# untitled.net
KiCad netlist of a schematic drawn in EAGLE
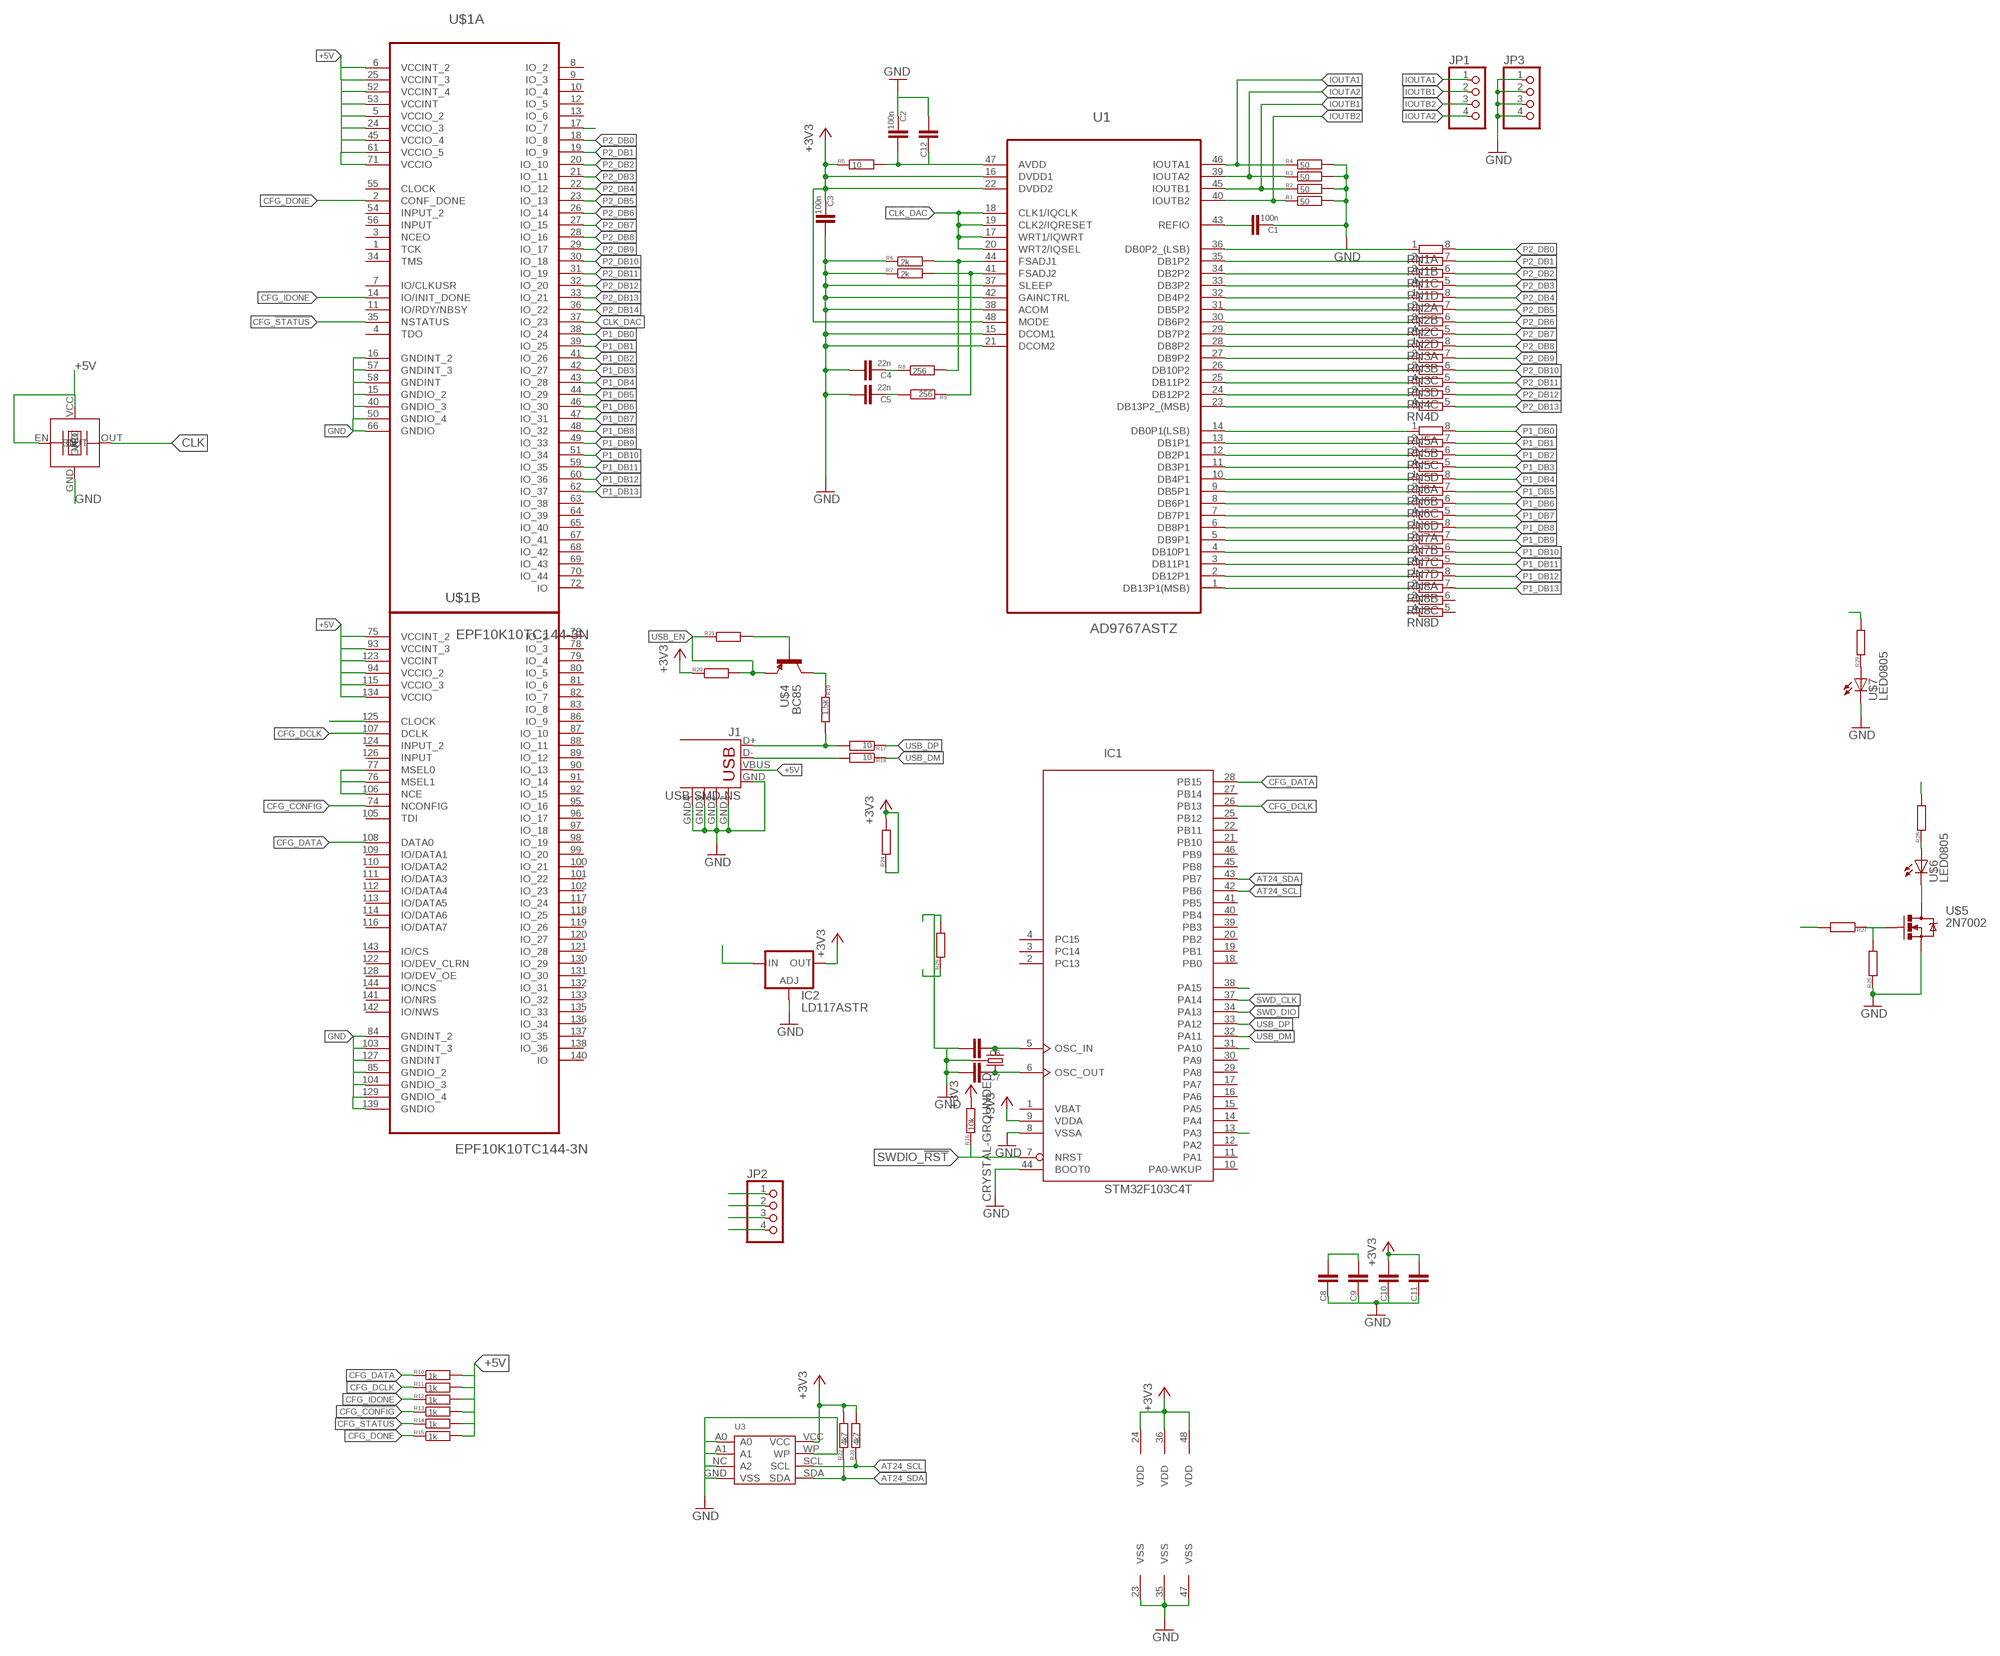
[diagram p0: schematic, sheet 1]

(export (version "E")
  (design (tool "Eeschema 10.0.6"))
  (components
    (comp (ref "C1")
      (value "100n")
      (footprint "eagle-import:C0805")
      (libsource (lib "eagle-import") (part "CC0805"))
    )
    (comp (ref "C2")
      (value "100n")
      (footprint "eagle-import:C0805")
      (libsource (lib "eagle-import") (part "CC0805"))
    )
    (comp (ref "C3")
      (value "100n")
      (footprint "eagle-import:C0805")
      (libsource (lib "eagle-import") (part "CC0805"))
    )
    (comp (ref "C4")
      (value "22n")
      (footprint "eagle-import:C0805")
      (libsource (lib "eagle-import") (part "CC0805"))
    )
    (comp (ref "C5")
      (value "22n")
      (footprint "eagle-import:C0805")
      (libsource (lib "eagle-import") (part "CC0805"))
    )
    (comp (ref "C6")
      (value "CC0603")
      (footprint "eagle-import:C0603")
      (libsource (lib "eagle-import") (part "CC0603"))
    )
    (comp (ref "C7")
      (value "CC0603")
      (footprint "eagle-import:C0603")
      (libsource (lib "eagle-import") (part "CC0603"))
    )
    (comp (ref "C8")
      (value "CC0805")
      (footprint "eagle-import:C0805")
      (libsource (lib "eagle-import") (part "CC0805"))
    )
    (comp (ref "C9")
      (value "CC0805")
      (footprint "eagle-import:C0805")
      (libsource (lib "eagle-import") (part "CC0805"))
    )
    (comp (ref "C10")
      (value "CC0805")
      (footprint "eagle-import:C0805")
      (libsource (lib "eagle-import") (part "CC0805"))
    )
    (comp (ref "C11")
      (value "CC0805")
      (footprint "eagle-import:C0805")
      (libsource (lib "eagle-import") (part "CC0805"))
    )
    (comp (ref "C12")
      (value "CC0805")
      (footprint "eagle-import:C0805")
      (libsource (lib "eagle-import") (part "CC0805"))
    )
    (comp (ref "IC1")
      (value "STM32F103C4T")
      (footprint "eagle-import:LQFP48")
      (libsource (lib "eagle-import") (part "STM32F103CT4"))
    )
    (comp (ref "IC2")
      (value "LD117ASTR")
      (footprint "eagle-import:SOT223")
      (libsource (lib "eagle-import") (part "LD117A?STR"))
    )
    (comp (ref "J1")
      (value "USB-SMD-NS")
      (footprint "eagle-import:USB-MINIB-NOSTOP")
      (libsource (lib "eagle-import") (part "USB-SMD-NS"))
    )
    (comp (ref "JP1")
      (value "PINHD-1X04_2.54")
      (footprint "eagle-import:1X04")
      (libsource (lib "eagle-import") (part "PINHD-1X04_2.54"))
    )
    (comp (ref "JP2")
      (value "PINHD-1X04_2.54")
      (footprint "eagle-import:1X04")
      (libsource (lib "eagle-import") (part "PINHD-1X04_2.54"))
    )
    (comp (ref "JP3")
      (value "PINHD-1X04_2.54")
      (footprint "eagle-import:1X04")
      (libsource (lib "eagle-import") (part "PINHD-1X04_2.54"))
    )
    (comp (ref "R1")
      (value "50")
      (footprint "eagle-import:R0805")
      (libsource (lib "eagle-import") (part "R0805"))
    )
    (comp (ref "R2")
      (value "50")
      (footprint "eagle-import:R0805")
      (libsource (lib "eagle-import") (part "R0805"))
    )
    (comp (ref "R3")
      (value "50")
      (footprint "eagle-import:R0805")
      (libsource (lib "eagle-import") (part "R0805"))
    )
    (comp (ref "R4")
      (value "50")
      (footprint "eagle-import:R0805")
      (libsource (lib "eagle-import") (part "R0805"))
    )
    (comp (ref "R5")
      (value "10")
      (footprint "eagle-import:R0805")
      (libsource (lib "eagle-import") (part "R0805"))
    )
    (comp (ref "R6")
      (value "2k")
      (footprint "eagle-import:R0805")
      (libsource (lib "eagle-import") (part "R0805"))
    )
    (comp (ref "R7")
      (value "2k")
      (footprint "eagle-import:R0805")
      (libsource (lib "eagle-import") (part "R0805"))
    )
    (comp (ref "R8")
      (value "256")
      (footprint "eagle-import:R0805")
      (libsource (lib "eagle-import") (part "R0805"))
    )
    (comp (ref "R9")
      (value "256")
      (footprint "eagle-import:R0805")
      (libsource (lib "eagle-import") (part "R0805"))
    )
    (comp (ref "R10")
      (value "1k")
      (footprint "eagle-import:0603")
      (libsource (lib "eagle-import") (part "R0603"))
    )
    (comp (ref "R11")
      (value "1k")
      (footprint "eagle-import:0603")
      (libsource (lib "eagle-import") (part "R0603"))
    )
    (comp (ref "R12")
      (value "1k")
      (footprint "eagle-import:0603")
      (libsource (lib "eagle-import") (part "R0603"))
    )
    (comp (ref "R13")
      (value "1k")
      (footprint "eagle-import:0603")
      (libsource (lib "eagle-import") (part "R0603"))
    )
    (comp (ref "R14")
      (value "1k")
      (footprint "eagle-import:0603")
      (libsource (lib "eagle-import") (part "R0603"))
    )
    (comp (ref "R15")
      (value "1k")
      (footprint "eagle-import:0603")
      (libsource (lib "eagle-import") (part "R0603"))
    )
    (comp (ref "R16")
      (value "10k")
      (footprint "eagle-import:0603")
      (libsource (lib "eagle-import") (part "R0603"))
    )
    (comp (ref "R17")
      (value "10")
      (footprint "eagle-import:0603")
      (libsource (lib "eagle-import") (part "R0603"))
    )
    (comp (ref "R18")
      (value "10")
      (footprint "eagle-import:0603")
      (libsource (lib "eagle-import") (part "R0603"))
    )
    (comp (ref "R19")
      (value "1.5k")
      (footprint "eagle-import:0603")
      (libsource (lib "eagle-import") (part "R0603"))
    )
    (comp (ref "R20")
      (value "R0603")
      (footprint "eagle-import:0603")
      (libsource (lib "eagle-import") (part "R0603"))
    )
    (comp (ref "R21")
      (value "R0603")
      (footprint "eagle-import:0603")
      (libsource (lib "eagle-import") (part "R0603"))
    )
    (comp (ref "R22")
      (value "4k7")
      (footprint "eagle-import:0603")
      (libsource (lib "eagle-import") (part "R0603"))
    )
    (comp (ref "R23")
      (value "4k7")
      (footprint "eagle-import:0603")
      (libsource (lib "eagle-import") (part "R0603"))
    )
    (comp (ref "R24")
      (value "R1206")
      (footprint "eagle-import:R1206")
      (libsource (lib "eagle-import") (part "R1206"))
    )
    (comp (ref "R25")
      (value "R0603")
      (footprint "eagle-import:0603")
      (libsource (lib "eagle-import") (part "R0603"))
    )
    (comp (ref "R26")
      (value "R0603")
      (footprint "eagle-import:0603")
      (libsource (lib "eagle-import") (part "R0603"))
    )
    (comp (ref "R27")
      (value "R0603")
      (footprint "eagle-import:0603")
      (libsource (lib "eagle-import") (part "R0603"))
    )
    (comp (ref "R28")
      (value "R0603")
      (footprint "eagle-import:0603")
      (libsource (lib "eagle-import") (part "R0603"))
    )
    (comp (ref "R29")
      (value "R0603")
      (footprint "eagle-import:0603")
      (libsource (lib "eagle-import") (part "R0603"))
    )
    (comp (ref "RN1")
      (value "4R-N0402ARV341")
      (footprint "eagle-import:4X0402ARV341")
      (libsource (lib "eagle-import") (part "4R-N0402ARV341"))
    )
    (comp (ref "RN2")
      (value "4R-N0402ARV341")
      (footprint "eagle-import:4X0402ARV341")
      (libsource (lib "eagle-import") (part "4R-N0402ARV341"))
    )
    (comp (ref "RN3")
      (value "4R-N0402ARV341")
      (footprint "eagle-import:4X0402ARV341")
      (libsource (lib "eagle-import") (part "4R-N0402ARV341"))
    )
    (comp (ref "RN4")
      (value "4R-N0402ARV341")
      (footprint "eagle-import:4X0402ARV341")
      (libsource (lib "eagle-import") (part "4R-N0402ARV341"))
    )
    (comp (ref "RN5")
      (value "4R-N0402ARV341")
      (footprint "eagle-import:4X0402ARV341")
      (libsource (lib "eagle-import") (part "4R-N0402ARV341"))
    )
    (comp (ref "RN6")
      (value "4R-N0402ARV341")
      (footprint "eagle-import:4X0402ARV341")
      (libsource (lib "eagle-import") (part "4R-N0402ARV341"))
    )
    (comp (ref "RN7")
      (value "4R-N0402ARV341")
      (footprint "eagle-import:4X0402ARV341")
      (libsource (lib "eagle-import") (part "4R-N0402ARV341"))
    )
    (comp (ref "RN8")
      (value "4R-N0402ARV341")
      (footprint "eagle-import:4X0402ARV341")
      (libsource (lib "eagle-import") (part "4R-N0402ARV341"))
    )
    (comp (ref "U$1")
      (value "EPF10K10TC144-3N")
      (footprint "eagle-import:QFP50P2200X2200X160-144N")
      (libsource (lib "eagle-import") (part "EPF10K10TC144-3N"))
    )
    (comp (ref "U$2")
      (value "TXC-BA")
      (footprint "eagle-import:7X5")
      (libsource (lib "eagle-import") (part "TXC-BA"))
    )
    (comp (ref "U$3")
      (value "CRYSTAL-GROUNDED")
      (footprint "eagle-import:CRYSTAL-SMD-5X3")
      (libsource (lib "eagle-import") (part "CRYSTAL-GROUNDED"))
    )
    (comp (ref "U$4")
      (value "BC85")
      (footprint "eagle-import:SOT23")
      (libsource (lib "eagle-import") (part "BC85"))
    )
    (comp (ref "U$5")
      (value "2N7002")
      (footprint "eagle-import:SOT23")
      (libsource (lib "eagle-import") (part "2N7002"))
    )
    (comp (ref "U$6")
      (value "LED0805")
      (footprint "eagle-import:0805-LED")
      (libsource (lib "eagle-import") (part "LED0805"))
    )
    (comp (ref "U$7")
      (value "LED0805")
      (footprint "eagle-import:0805-LED")
      (libsource (lib "eagle-import") (part "LED0805"))
    )
    (comp (ref "U1")
      (value "AD9767ASTZ")
      (footprint "eagle-import:QFP50P900X900X160-48N")
      (libsource (lib "eagle-import") (part "AD9767ASTZ"))
    )
    (comp (ref "U3")
      (value "EEPROM-CAT24C256WI-GT3(SOIC8)QFN")
      (footprint "eagle-import:QFN")
      (libsource (lib "eagle-import") (part "EEPROM-CAT24C256WI-GT3(SOIC8)QFN"))
    )
  )
  (nets
    (net (code "1") (name "+3V3") (class "Default")
      (node (ref "C10") (pin "1") (pinfunction "1_1") (pintype "passive"))
      (node (ref "C11") (pin "1") (pinfunction "1_1") (pintype "passive"))
      (node (ref "C3") (pin "2") (pinfunction "2_2") (pintype "passive"))
      (node (ref "IC1") (pin "24") (pinfunction "VDD_24") (pintype "power_in"))
      (node (ref "IC1") (pin "36") (pinfunction "VDD_36") (pintype "power_in"))
      (node (ref "IC1") (pin "48") (pinfunction "VDD_48") (pintype "power_in"))
      (node (ref "IC1") (pin "9") (pinfunction "VDDA_9") (pintype "power_in"))
      (node (ref "IC2") (pin "4") (pinfunction "OUT_4") (pintype "passive"))
      (node (ref "R16") (pin "2") (pinfunction "2_2") (pintype "passive"))
      (node (ref "R20") (pin "1") (pinfunction "1_1") (pintype "passive"))
      (node (ref "R22") (pin "2") (pinfunction "2_2") (pintype "passive"))
      (node (ref "R23") (pin "2") (pinfunction "2_2") (pintype "passive"))
      (node (ref "R24") (pin "1") (pinfunction "1_1") (pintype "passive"))
      (node (ref "R24") (pin "2") (pinfunction "2_2") (pintype "passive"))
      (node (ref "R5") (pin "1") (pinfunction "1_1") (pintype "passive"))
      (node (ref "U1") (pin "16") (pinfunction "DVDD1_16") (pintype "power_in"))
      (node (ref "U1") (pin "22") (pinfunction "DVDD2_22") (pintype "power_in"))
      (node (ref "U1") (pin "48") (pinfunction "MODE_48") (pintype "passive"))
      (node (ref "U3") (pin "VCC") (pinfunction "VCC_VCC") (pintype "bidirectional"))
    )
    (net (code "2") (name "+5V") (class "Default")
      (node (ref "C8") (pin "1") (pinfunction "1_1") (pintype "passive"))
      (node (ref "C9") (pin "1") (pinfunction "1_1") (pintype "passive"))
      (node (ref "IC2") (pin "3") (pinfunction "IN_3") (pintype "input"))
      (node (ref "J1") (pin "VBUS") (pinfunction "VBUS_VBUS") (pintype "bidirectional"))
      (node (ref "R10") (pin "2") (pinfunction "2_2") (pintype "passive"))
      (node (ref "R11") (pin "2") (pinfunction "2_2") (pintype "passive"))
      (node (ref "R12") (pin "2") (pinfunction "2_2") (pintype "passive"))
      (node (ref "R13") (pin "2") (pinfunction "2_2") (pintype "passive"))
      (node (ref "R14") (pin "2") (pinfunction "2_2") (pintype "passive"))
      (node (ref "R15") (pin "2") (pinfunction "2_2") (pintype "passive"))
      (node (ref "R28") (pin "2") (pinfunction "2_2") (pintype "passive"))
      (node (ref "U$1") (pin "115") (pinfunction "VCCIO_3_115") (pintype "power_in"))
      (node (ref "U$1") (pin "123") (pinfunction "VCCINT_123") (pintype "power_in"))
      (node (ref "U$1") (pin "134") (pinfunction "VCCIO_134") (pintype "power_in"))
      (node (ref "U$1") (pin "24") (pinfunction "VCCIO_3_24") (pintype "power_in"))
      (node (ref "U$1") (pin "25") (pinfunction "VCCINT_3_25") (pintype "power_in"))
      (node (ref "U$1") (pin "45") (pinfunction "VCCIO_4_45") (pintype "power_in"))
      (node (ref "U$1") (pin "5") (pinfunction "VCCIO_2_5") (pintype "power_in"))
      (node (ref "U$1") (pin "52") (pinfunction "VCCINT_4_52") (pintype "power_in"))
      (node (ref "U$1") (pin "53") (pinfunction "VCCINT_53") (pintype "power_in"))
      (node (ref "U$1") (pin "6") (pinfunction "VCCINT_2_6") (pintype "power_in"))
      (node (ref "U$1") (pin "61") (pinfunction "VCCIO_5_61") (pintype "power_in"))
      (node (ref "U$1") (pin "71") (pinfunction "VCCIO_71") (pintype "power_in"))
      (node (ref "U$1") (pin "75") (pinfunction "VCCINT_2_75") (pintype "power_in"))
      (node (ref "U$1") (pin "93") (pinfunction "VCCINT_3_93") (pintype "power_in"))
      (node (ref "U$1") (pin "94") (pinfunction "VCCIO_2_94") (pintype "power_in"))
      (node (ref "U$2") (pin "EN") (pinfunction "EN_EN") (pintype "bidirectional"))
      (node (ref "U$2") (pin "VCC") (pinfunction "VCC_VCC") (pintype "bidirectional"))
    )
    (net (code "3") (name "/CFG_~{CONFIG}") (class "Default")
      (node (ref "IC1") (pin "31") (pinfunction "PA10_31") (pintype "bidirectional"))
      (node (ref "R13") (pin "1") (pinfunction "1_1") (pintype "passive"))
      (node (ref "U$1") (pin "74") (pinfunction "NCONFIG_74") (pintype "input"))
    )
    (net (code "4") (name "/CFG_~{STATUS}") (class "Default")
      (node (ref "R14") (pin "1") (pinfunction "1_1") (pintype "passive"))
      (node (ref "U$1") (pin "35") (pinfunction "NSTATUS_35") (pintype "output"))
    )
    (net (code "5") (name "/IO7") (class "Default")
      (node (ref "R29") (pin "2") (pinfunction "2_2") (pintype "passive"))
      (node (ref "U$1") (pin "17") (pinfunction "IO_7_17") (pintype "bidirectional"))
    )
    (net (code "6") (name "/SWDIO_~{RST}") (class "Default")
      (node (ref "IC1") (pin "7") (pinfunction "NRST_7") (pintype "bidirectional"))
      (node (ref "JP2") (pin "4") (pinfunction "4_4") (pintype "passive"))
      (node (ref "R16") (pin "1") (pinfunction "1_1") (pintype "passive"))
    )
    (net (code "7") (name "/VBAT") (class "Default")
      (node (ref "IC1") (pin "1") (pinfunction "VBAT_1") (pintype "power_in"))
    )
    (net (code "8") (name "AT24_SCL") (class "Default")
      (node (ref "IC1") (pin "42") (pinfunction "PB6_42") (pintype "bidirectional"))
      (node (ref "R23") (pin "1") (pinfunction "1_1") (pintype "passive"))
      (node (ref "U3") (pin "SCL") (pinfunction "SCL_SCL") (pintype "bidirectional"))
    )
    (net (code "9") (name "AT24_SDA") (class "Default")
      (node (ref "IC1") (pin "43") (pinfunction "PB7_43") (pintype "bidirectional"))
      (node (ref "R22") (pin "1") (pinfunction "1_1") (pintype "passive"))
      (node (ref "U3") (pin "SDA") (pinfunction "SDA_SDA") (pintype "bidirectional"))
    )
    (net (code "10") (name "CFG_DATA") (class "Default")
      (node (ref "IC1") (pin "28") (pinfunction "PB15_28") (pintype "bidirectional"))
      (node (ref "R10") (pin "1") (pinfunction "1_1") (pintype "passive"))
      (node (ref "U$1") (pin "108") (pinfunction "DATA0_108") (pintype "bidirectional"))
    )
    (net (code "11") (name "CFG_DCLK") (class "Default")
      (node (ref "IC1") (pin "26") (pinfunction "PB13_26") (pintype "bidirectional"))
      (node (ref "R11") (pin "1") (pinfunction "1_1") (pintype "passive"))
      (node (ref "U$1") (pin "107") (pinfunction "DCLK_107") (pintype "input"))
    )
    (net (code "12") (name "CFG_DONE") (class "Default")
      (node (ref "R15") (pin "1") (pinfunction "1_1") (pintype "passive"))
      (node (ref "R27") (pin "2") (pinfunction "2_2") (pintype "passive"))
      (node (ref "U$1") (pin "2") (pinfunction "CONF_DONE_2") (pintype "input"))
    )
    (net (code "13") (name "CFG_IDONE") (class "Default")
      (node (ref "R12") (pin "1") (pinfunction "1_1") (pintype "passive"))
      (node (ref "U$1") (pin "14") (pinfunction "IO/INIT_DONE_14") (pintype "bidirectional"))
    )
    (net (code "14") (name "CLK") (class "Default")
      (node (ref "U$1") (pin "125") (pinfunction "CLOCK_125") (pintype "input"))
      (node (ref "U$2") (pin "OUT") (pinfunction "OUT_OUT") (pintype "bidirectional"))
    )
    (net (code "15") (name "CLK_DAC") (class "Default")
      (node (ref "U$1") (pin "37") (pinfunction "IO_23_37") (pintype "bidirectional"))
      (node (ref "U1") (pin "17") (pinfunction "WRT1/IQWRT_17") (pintype "input"))
      (node (ref "U1") (pin "18") (pinfunction "CLK1/IQCLK_18") (pintype "input"))
      (node (ref "U1") (pin "19") (pinfunction "CLK2/IQRESET_19") (pintype "input"))
      (node (ref "U1") (pin "20") (pinfunction "WRT2/IQSEL_20") (pintype "input"))
    )
    (net (code "16") (name "GND") (class "Default")
      (node (ref "C1") (pin "2") (pinfunction "2_2") (pintype "passive"))
      (node (ref "C10") (pin "2") (pinfunction "2_2") (pintype "passive"))
      (node (ref "C11") (pin "2") (pinfunction "2_2") (pintype "passive"))
      (node (ref "C12") (pin "1") (pinfunction "1_1") (pintype "passive"))
      (node (ref "C2") (pin "2") (pinfunction "2_2") (pintype "passive"))
      (node (ref "C3") (pin "1") (pinfunction "1_1") (pintype "passive"))
      (node (ref "C4") (pin "1") (pinfunction "1_1") (pintype "passive"))
      (node (ref "C5") (pin "1") (pinfunction "1_1") (pintype "passive"))
      (node (ref "C6") (pin "1") (pinfunction "1_1") (pintype "passive"))
      (node (ref "C7") (pin "1") (pinfunction "1_1") (pintype "passive"))
      (node (ref "C8") (pin "2") (pinfunction "2_2") (pintype "passive"))
      (node (ref "C9") (pin "2") (pinfunction "2_2") (pintype "passive"))
      (node (ref "IC1") (pin "23") (pinfunction "VSS_23") (pintype "power_in"))
      (node (ref "IC1") (pin "35") (pinfunction "VSS_35") (pintype "power_in"))
      (node (ref "IC1") (pin "38") (pinfunction "PA15_38") (pintype "bidirectional"))
      (node (ref "IC1") (pin "44") (pinfunction "BOOT0_44") (pintype "input"))
      (node (ref "IC1") (pin "47") (pinfunction "VSS_47") (pintype "power_in"))
      (node (ref "IC1") (pin "8") (pinfunction "VSSA_8") (pintype "power_in"))
      (node (ref "IC2") (pin "1") (pinfunction "ADJ_1") (pintype "input"))
      (node (ref "J1") (pin "GND") (pinfunction "GND_GND") (pintype "bidirectional"))
      (node (ref "J1") (pin "GND1") (pinfunction "GND_GND1") (pintype "bidirectional"))
      (node (ref "J1") (pin "GND2") (pinfunction "GND_GND2") (pintype "bidirectional"))
      (node (ref "J1") (pin "GND3") (pinfunction "GND_GND3") (pintype "bidirectional"))
      (node (ref "J1") (pin "GND4") (pinfunction "GND_GND4") (pintype "bidirectional"))
      (node (ref "JP2") (pin "1") (pinfunction "1_1") (pintype "passive"))
      (node (ref "JP3") (pin "1") (pinfunction "1_1") (pintype "passive"))
      (node (ref "JP3") (pin "2") (pinfunction "2_2") (pintype "passive"))
      (node (ref "JP3") (pin "3") (pinfunction "3_3") (pintype "passive"))
      (node (ref "JP3") (pin "4") (pinfunction "4_4") (pintype "passive"))
      (node (ref "R1") (pin "2") (pinfunction "2_2") (pintype "passive"))
      (node (ref "R2") (pin "2") (pinfunction "2_2") (pintype "passive"))
      (node (ref "R25") (pin "1") (pinfunction "1_1") (pintype "passive"))
      (node (ref "R26") (pin "1") (pinfunction "1_1") (pintype "passive"))
      (node (ref "R26") (pin "2") (pinfunction "2_2") (pintype "passive"))
      (node (ref "R3") (pin "2") (pinfunction "2_2") (pintype "passive"))
      (node (ref "R4") (pin "2") (pinfunction "2_2") (pintype "passive"))
      (node (ref "R6") (pin "1") (pinfunction "1_1") (pintype "passive"))
      (node (ref "R7") (pin "1") (pinfunction "1_1") (pintype "passive"))
      (node (ref "U$1") (pin "103") (pinfunction "GNDINT_3_103") (pintype "passive"))
      (node (ref "U$1") (pin "104") (pinfunction "GNDIO_3_104") (pintype "passive"))
      (node (ref "U$1") (pin "106") (pinfunction "NCE_106") (pintype "input"))
      (node (ref "U$1") (pin "127") (pinfunction "GNDINT_127") (pintype "passive"))
      (node (ref "U$1") (pin "129") (pinfunction "GNDIO_4_129") (pintype "passive"))
      (node (ref "U$1") (pin "139") (pinfunction "GNDIO_139") (pintype "passive"))
      (node (ref "U$1") (pin "15") (pinfunction "GNDIO_2_15") (pintype "passive"))
      (node (ref "U$1") (pin "16") (pinfunction "GNDINT_2_16") (pintype "passive"))
      (node (ref "U$1") (pin "40") (pinfunction "GNDIO_3_40") (pintype "passive"))
      (node (ref "U$1") (pin "50") (pinfunction "GNDIO_4_50") (pintype "passive"))
      (node (ref "U$1") (pin "57") (pinfunction "GNDINT_3_57") (pintype "passive"))
      (node (ref "U$1") (pin "58") (pinfunction "GNDINT_58") (pintype "passive"))
      (node (ref "U$1") (pin "66") (pinfunction "GNDIO_66") (pintype "passive"))
      (node (ref "U$1") (pin "76") (pinfunction "MSEL1_76") (pintype "input"))
      (node (ref "U$1") (pin "77") (pinfunction "MSEL0_77") (pintype "input"))
      (node (ref "U$1") (pin "84") (pinfunction "GNDINT_2_84") (pintype "passive"))
      (node (ref "U$1") (pin "85") (pinfunction "GNDIO_2_85") (pintype "passive"))
      (node (ref "U$2") (pin "GND") (pinfunction "GND_GND") (pintype "bidirectional"))
      (node (ref "U$3") (pin "2") (pinfunction "3_2") (pintype "passive"))
      (node (ref "U$3") (pin "4") (pinfunction "3_4") (pintype "passive"))
      (node (ref "U$5") (pin "2") (pinfunction "S_2") (pintype "passive"))
      (node (ref "U$7") (pin "C") (pinfunction "C_C") (pintype "passive"))
      (node (ref "U1") (pin "15") (pinfunction "DCOM1_15") (pintype "passive"))
      (node (ref "U1") (pin "21") (pinfunction "DCOM2_21") (pintype "passive"))
      (node (ref "U1") (pin "37") (pinfunction "SLEEP_37") (pintype "passive"))
      (node (ref "U1") (pin "38") (pinfunction "ACOM_38") (pintype "passive"))
      (node (ref "U1") (pin "42") (pinfunction "GAINCTRL_42") (pintype "passive"))
      (node (ref "U3") (pin "A0") (pinfunction "A0_A0") (pintype "bidirectional"))
      (node (ref "U3") (pin "A1") (pinfunction "A1_A1") (pintype "bidirectional"))
      (node (ref "U3") (pin "GND") (pinfunction "VSS_GND") (pintype "bidirectional"))
      (node (ref "U3") (pin "NC") (pinfunction "A2_NC") (pintype "bidirectional"))
      (node (ref "U3") (pin "WP") (pinfunction "WP_WP") (pintype "bidirectional"))
    )
    (net (code "17") (name "IOUTA1") (class "Default")
      (node (ref "JP1") (pin "1") (pinfunction "1_1") (pintype "passive"))
      (node (ref "R4") (pin "1") (pinfunction "1_1") (pintype "passive"))
      (node (ref "U1") (pin "46") (pinfunction "IOUTA1_46") (pintype "output"))
    )
    (net (code "18") (name "IOUTA2") (class "Default")
      (node (ref "JP1") (pin "4") (pinfunction "4_4") (pintype "passive"))
      (node (ref "R3") (pin "1") (pinfunction "1_1") (pintype "passive"))
      (node (ref "U1") (pin "39") (pinfunction "IOUTA2_39") (pintype "output"))
    )
    (net (code "19") (name "IOUTB1") (class "Default")
      (node (ref "JP1") (pin "2") (pinfunction "2_2") (pintype "passive"))
      (node (ref "R2") (pin "1") (pinfunction "1_1") (pintype "passive"))
      (node (ref "U1") (pin "45") (pinfunction "IOUTB1_45") (pintype "output"))
    )
    (net (code "20") (name "IOUTB2") (class "Default")
      (node (ref "JP1") (pin "3") (pinfunction "3_3") (pintype "passive"))
      (node (ref "R1") (pin "1") (pinfunction "1_1") (pintype "passive"))
      (node (ref "U1") (pin "40") (pinfunction "IOUTB2_40") (pintype "output"))
    )
    (net (code "21") (name "Net-(C4-Pad2)") (class "Default")
      (node (ref "C4") (pin "2") (pinfunction "2_2") (pintype "passive"))
      (node (ref "R8") (pin "1") (pinfunction "1_1") (pintype "passive"))
    )
    (net (code "22") (name "Net-(C5-Pad2)") (class "Default")
      (node (ref "C5") (pin "2") (pinfunction "2_2") (pintype "passive"))
      (node (ref "R9") (pin "2") (pinfunction "2_2") (pintype "passive"))
    )
    (net (code "23") (name "Net-(IC1A-OSC_IN)") (class "Default")
      (node (ref "C6") (pin "2") (pinfunction "2_2") (pintype "passive"))
      (node (ref "IC1") (pin "5") (pinfunction "OSC_IN_5") (pintype "bidirectional"))
      (node (ref "U$3") (pin "3") (pinfunction "1_3") (pintype "passive"))
    )
    (net (code "24") (name "Net-(IC1A-OSC_OUT)") (class "Default")
      (node (ref "C7") (pin "2") (pinfunction "2_2") (pintype "passive"))
      (node (ref "IC1") (pin "6") (pinfunction "OSC_OUT_6") (pintype "bidirectional"))
      (node (ref "U$3") (pin "1") (pinfunction "2_1") (pintype "passive"))
    )
    (net (code "25") (name "Net-(J1-PadD+)") (class "Default")
      (node (ref "J1") (pin "D+") (pinfunction "D+_D+") (pintype "bidirectional"))
      (node (ref "R17") (pin "2") (pinfunction "2_2") (pintype "passive"))
      (node (ref "R19") (pin "2") (pinfunction "2_2") (pintype "passive"))
    )
    (net (code "26") (name "Net-(J1-PadD-)") (class "Default")
      (node (ref "J1") (pin "D-") (pinfunction "D-_D-") (pintype "bidirectional"))
      (node (ref "R18") (pin "2") (pinfunction "2_2") (pintype "passive"))
    )
    (net (code "27") (name "Net-(R28-Pad1)") (class "Default")
      (node (ref "R28") (pin "1") (pinfunction "1_1") (pintype "passive"))
      (node (ref "U$6") (pin "A") (pinfunction "A_A") (pintype "passive"))
    )
    (net (code "28") (name "Net-(R29-Pad1)") (class "Default")
      (node (ref "R29") (pin "1") (pinfunction "1_1") (pintype "passive"))
      (node (ref "U$7") (pin "A") (pinfunction "A_A") (pintype "passive"))
    )
    (net (code "29") (name "Net-(RN1B-1)") (class "Default")
      (node (ref "RN1") (pin "2") (pinfunction "1_2") (pintype "passive"))
      (node (ref "U1") (pin "35") (pinfunction "DB1P2_35") (pintype "bidirectional"))
    )
    (net (code "30") (name "Net-(RN1C-1)") (class "Default")
      (node (ref "RN1") (pin "3") (pinfunction "1_3") (pintype "passive"))
      (node (ref "U1") (pin "34") (pinfunction "DB2P2_34") (pintype "bidirectional"))
    )
    (net (code "31") (name "Net-(RN1D-1)") (class "Default")
      (node (ref "RN1") (pin "4") (pinfunction "1_4") (pintype "passive"))
      (node (ref "U1") (pin "33") (pinfunction "DB3P2_33") (pintype "bidirectional"))
    )
    (net (code "32") (name "Net-(RN2B-1)") (class "Default")
      (node (ref "RN2") (pin "2") (pinfunction "1_2") (pintype "passive"))
      (node (ref "U1") (pin "31") (pinfunction "DB5P2_31") (pintype "bidirectional"))
    )
    (net (code "33") (name "Net-(RN2C-1)") (class "Default")
      (node (ref "RN2") (pin "3") (pinfunction "1_3") (pintype "passive"))
      (node (ref "U1") (pin "30") (pinfunction "DB6P2_30") (pintype "bidirectional"))
    )
    (net (code "34") (name "Net-(RN2D-1)") (class "Default")
      (node (ref "RN2") (pin "4") (pinfunction "1_4") (pintype "passive"))
      (node (ref "U1") (pin "29") (pinfunction "DB7P2_29") (pintype "bidirectional"))
    )
    (net (code "35") (name "Net-(RN3B-1)") (class "Default")
      (node (ref "RN3") (pin "2") (pinfunction "1_2") (pintype "passive"))
      (node (ref "U1") (pin "27") (pinfunction "DB9P2_27") (pintype "bidirectional"))
    )
    (net (code "36") (name "Net-(RN3C-1)") (class "Default")
      (node (ref "RN3") (pin "3") (pinfunction "1_3") (pintype "passive"))
      (node (ref "U1") (pin "26") (pinfunction "DB10P2_26") (pintype "bidirectional"))
    )
    (net (code "37") (name "Net-(RN3D-1)") (class "Default")
      (node (ref "RN3") (pin "4") (pinfunction "1_4") (pintype "passive"))
      (node (ref "U1") (pin "25") (pinfunction "DB11P2_25") (pintype "bidirectional"))
    )
    (net (code "38") (name "Net-(RN4C-1)") (class "Default")
      (node (ref "RN4") (pin "3") (pinfunction "1_3") (pintype "passive"))
      (node (ref "U1") (pin "24") (pinfunction "DB12P2_24") (pintype "bidirectional"))
    )
    (net (code "39") (name "Net-(RN4D-1)") (class "Default")
      (node (ref "RN4") (pin "4") (pinfunction "1_4") (pintype "passive"))
      (node (ref "U1") (pin "23") (pinfunction "DB13P2_(MSB)_23") (pintype "bidirectional"))
    )
    (net (code "40") (name "Net-(RN5B-1)") (class "Default")
      (node (ref "RN5") (pin "2") (pinfunction "1_2") (pintype "passive"))
      (node (ref "U1") (pin "13") (pinfunction "DB1P1_13") (pintype "bidirectional"))
    )
    (net (code "41") (name "Net-(RN5C-1)") (class "Default")
      (node (ref "RN5") (pin "3") (pinfunction "1_3") (pintype "passive"))
      (node (ref "U1") (pin "12") (pinfunction "DB2P1_12") (pintype "bidirectional"))
    )
    (net (code "42") (name "Net-(RN5D-1)") (class "Default")
      (node (ref "RN5") (pin "4") (pinfunction "1_4") (pintype "passive"))
      (node (ref "U1") (pin "11") (pinfunction "DB3P1_11") (pintype "bidirectional"))
    )
    (net (code "43") (name "Net-(RN6B-1)") (class "Default")
      (node (ref "RN6") (pin "2") (pinfunction "1_2") (pintype "passive"))
      (node (ref "U1") (pin "9") (pinfunction "DB5P1_9") (pintype "bidirectional"))
    )
    (net (code "44") (name "Net-(RN6C-1)") (class "Default")
      (node (ref "RN6") (pin "3") (pinfunction "1_3") (pintype "passive"))
      (node (ref "U1") (pin "8") (pinfunction "DB6P1_8") (pintype "bidirectional"))
    )
    (net (code "45") (name "Net-(RN6D-1)") (class "Default")
      (node (ref "RN6") (pin "4") (pinfunction "1_4") (pintype "passive"))
      (node (ref "U1") (pin "7") (pinfunction "DB7P1_7") (pintype "bidirectional"))
    )
    (net (code "46") (name "Net-(RN7B-1)") (class "Default")
      (node (ref "RN7") (pin "2") (pinfunction "1_2") (pintype "passive"))
      (node (ref "U1") (pin "5") (pinfunction "DB9P1_5") (pintype "bidirectional"))
    )
    (net (code "47") (name "Net-(RN7C-1)") (class "Default")
      (node (ref "RN7") (pin "3") (pinfunction "1_3") (pintype "passive"))
      (node (ref "U1") (pin "4") (pinfunction "DB10P1_4") (pintype "bidirectional"))
    )
    (net (code "48") (name "Net-(RN7D-1)") (class "Default")
      (node (ref "RN7") (pin "4") (pinfunction "1_4") (pintype "passive"))
      (node (ref "U1") (pin "3") (pinfunction "DB11P1_3") (pintype "bidirectional"))
    )
    (net (code "49") (name "Net-(RN8B-1)") (class "Default")
      (node (ref "RN8") (pin "2") (pinfunction "1_2") (pintype "passive"))
      (node (ref "U1") (pin "1") (pinfunction "DB13P1(MSB)_1") (pintype "bidirectional"))
    )
    (net (code "50") (name "Net-(U$4-B)") (class "Default")
      (node (ref "R21") (pin "2") (pinfunction "2_2") (pintype "passive"))
      (node (ref "U$4") (pin "1") (pinfunction "B_1") (pintype "passive"))
    )
    (net (code "51") (name "Net-(U$4-C)") (class "Default")
      (node (ref "R19") (pin "1") (pinfunction "1_1") (pintype "passive"))
      (node (ref "U$4") (pin "3") (pinfunction "C_3") (pintype "passive"))
    )
    (net (code "52") (name "Net-(U$5-D)") (class "Default")
      (node (ref "U$5") (pin "3") (pinfunction "D_3") (pintype "passive"))
      (node (ref "U$6") (pin "C") (pinfunction "C_C") (pintype "passive"))
    )
    (net (code "53") (name "Net-(U$5-G)") (class "Default")
      (node (ref "R25") (pin "2") (pinfunction "2_2") (pintype "passive"))
      (node (ref "R27") (pin "1") (pinfunction "1_1") (pintype "passive"))
      (node (ref "U$5") (pin "1") (pinfunction "G_1") (pintype "passive"))
    )
    (net (code "54") (name "Net-(U1-AVDD)") (class "Default")
      (node (ref "C12") (pin "2") (pinfunction "2_2") (pintype "passive"))
      (node (ref "C2") (pin "1") (pinfunction "1_1") (pintype "passive"))
      (node (ref "R5") (pin "2") (pinfunction "2_2") (pintype "passive"))
      (node (ref "U1") (pin "47") (pinfunction "AVDD_47") (pintype "power_in"))
    )
    (net (code "55") (name "Net-(U1-DB0P1(LSB))") (class "Default")
      (node (ref "RN5") (pin "1") (pinfunction "1_1") (pintype "passive"))
      (node (ref "U1") (pin "14") (pinfunction "DB0P1(LSB)_14") (pintype "bidirectional"))
    )
    (net (code "56") (name "Net-(U1-DB0P2_(LSB))") (class "Default")
      (node (ref "RN1") (pin "1") (pinfunction "1_1") (pintype "passive"))
      (node (ref "U1") (pin "36") (pinfunction "DB0P2_(LSB)_36") (pintype "bidirectional"))
    )
    (net (code "57") (name "Net-(U1-DB4P1)") (class "Default")
      (node (ref "RN6") (pin "1") (pinfunction "1_1") (pintype "passive"))
      (node (ref "U1") (pin "10") (pinfunction "DB4P1_10") (pintype "bidirectional"))
    )
    (net (code "58") (name "Net-(U1-DB4P2)") (class "Default")
      (node (ref "RN2") (pin "1") (pinfunction "1_1") (pintype "passive"))
      (node (ref "U1") (pin "32") (pinfunction "DB4P2_32") (pintype "bidirectional"))
    )
    (net (code "59") (name "Net-(U1-DB8P1)") (class "Default")
      (node (ref "RN7") (pin "1") (pinfunction "1_1") (pintype "passive"))
      (node (ref "U1") (pin "6") (pinfunction "DB8P1_6") (pintype "bidirectional"))
    )
    (net (code "60") (name "Net-(U1-DB8P2)") (class "Default")
      (node (ref "RN3") (pin "1") (pinfunction "1_1") (pintype "passive"))
      (node (ref "U1") (pin "28") (pinfunction "DB8P2_28") (pintype "bidirectional"))
    )
    (net (code "61") (name "Net-(U1-DB12P1)") (class "Default")
      (node (ref "RN8") (pin "1") (pinfunction "1_1") (pintype "passive"))
      (node (ref "U1") (pin "2") (pinfunction "DB12P1_2") (pintype "bidirectional"))
    )
    (net (code "62") (name "Net-(U1-FSADJ1)") (class "Default")
      (node (ref "R6") (pin "2") (pinfunction "2_2") (pintype "passive"))
      (node (ref "R8") (pin "2") (pinfunction "2_2") (pintype "passive"))
      (node (ref "U1") (pin "44") (pinfunction "FSADJ1_44") (pintype "passive"))
    )
    (net (code "63") (name "Net-(U1-FSADJ2)") (class "Default")
      (node (ref "R7") (pin "2") (pinfunction "2_2") (pintype "passive"))
      (node (ref "R9") (pin "1") (pinfunction "1_1") (pintype "passive"))
      (node (ref "U1") (pin "41") (pinfunction "FSADJ2_41") (pintype "passive"))
    )
    (net (code "64") (name "Net-(U1-REFIO)") (class "Default")
      (node (ref "C1") (pin "1") (pinfunction "1_1") (pintype "passive"))
      (node (ref "U1") (pin "43") (pinfunction "REFIO_43") (pintype "bidirectional"))
    )
    (net (code "65") (name "P1_DB0") (class "Default")
      (node (ref "RN5") (pin "8") (pinfunction "2_8") (pintype "passive"))
      (node (ref "U$1") (pin "38") (pinfunction "IO_24_38") (pintype "bidirectional"))
    )
    (net (code "66") (name "P1_DB1") (class "Default")
      (node (ref "RN5") (pin "7") (pinfunction "2_7") (pintype "passive"))
      (node (ref "U$1") (pin "39") (pinfunction "IO_25_39") (pintype "bidirectional"))
    )
    (net (code "67") (name "P1_DB2") (class "Default")
      (node (ref "RN5") (pin "6") (pinfunction "2_6") (pintype "passive"))
      (node (ref "U$1") (pin "41") (pinfunction "IO_26_41") (pintype "bidirectional"))
    )
    (net (code "68") (name "P1_DB3") (class "Default")
      (node (ref "RN5") (pin "5") (pinfunction "2_5") (pintype "passive"))
      (node (ref "U$1") (pin "42") (pinfunction "IO_27_42") (pintype "bidirectional"))
    )
    (net (code "69") (name "P1_DB4") (class "Default")
      (node (ref "RN6") (pin "8") (pinfunction "2_8") (pintype "passive"))
      (node (ref "U$1") (pin "43") (pinfunction "IO_28_43") (pintype "bidirectional"))
    )
    (net (code "70") (name "P1_DB5") (class "Default")
      (node (ref "RN6") (pin "7") (pinfunction "2_7") (pintype "passive"))
      (node (ref "U$1") (pin "44") (pinfunction "IO_29_44") (pintype "bidirectional"))
    )
    (net (code "71") (name "P1_DB6") (class "Default")
      (node (ref "RN6") (pin "6") (pinfunction "2_6") (pintype "passive"))
      (node (ref "U$1") (pin "46") (pinfunction "IO_30_46") (pintype "bidirectional"))
    )
    (net (code "72") (name "P1_DB7") (class "Default")
      (node (ref "RN6") (pin "5") (pinfunction "2_5") (pintype "passive"))
      (node (ref "U$1") (pin "47") (pinfunction "IO_31_47") (pintype "bidirectional"))
    )
    (net (code "73") (name "P1_DB8") (class "Default")
      (node (ref "RN7") (pin "8") (pinfunction "2_8") (pintype "passive"))
      (node (ref "U$1") (pin "48") (pinfunction "IO_32_48") (pintype "bidirectional"))
    )
    (net (code "74") (name "P1_DB9") (class "Default")
      (node (ref "RN7") (pin "7") (pinfunction "2_7") (pintype "passive"))
      (node (ref "U$1") (pin "49") (pinfunction "IO_33_49") (pintype "bidirectional"))
    )
    (net (code "75") (name "P1_DB10") (class "Default")
      (node (ref "RN7") (pin "6") (pinfunction "2_6") (pintype "passive"))
      (node (ref "U$1") (pin "51") (pinfunction "IO_34_51") (pintype "bidirectional"))
    )
    (net (code "76") (name "P1_DB11") (class "Default")
      (node (ref "RN7") (pin "5") (pinfunction "2_5") (pintype "passive"))
      (node (ref "U$1") (pin "59") (pinfunction "IO_35_59") (pintype "bidirectional"))
    )
    (net (code "77") (name "P1_DB12") (class "Default")
      (node (ref "RN8") (pin "8") (pinfunction "2_8") (pintype "passive"))
      (node (ref "U$1") (pin "60") (pinfunction "IO_36_60") (pintype "bidirectional"))
    )
    (net (code "78") (name "P1_DB13") (class "Default")
      (node (ref "RN8") (pin "7") (pinfunction "2_7") (pintype "passive"))
      (node (ref "U$1") (pin "62") (pinfunction "IO_37_62") (pintype "bidirectional"))
    )
    (net (code "79") (name "P2_DB0") (class "Default")
      (node (ref "RN1") (pin "8") (pinfunction "2_8") (pintype "passive"))
      (node (ref "U$1") (pin "18") (pinfunction "IO_8_18") (pintype "bidirectional"))
    )
    (net (code "80") (name "P2_DB1") (class "Default")
      (node (ref "RN1") (pin "7") (pinfunction "2_7") (pintype "passive"))
      (node (ref "U$1") (pin "19") (pinfunction "IO_9_19") (pintype "bidirectional"))
    )
    (net (code "81") (name "P2_DB2") (class "Default")
      (node (ref "RN1") (pin "6") (pinfunction "2_6") (pintype "passive"))
      (node (ref "U$1") (pin "20") (pinfunction "IO_10_20") (pintype "bidirectional"))
    )
    (net (code "82") (name "P2_DB3") (class "Default")
      (node (ref "RN1") (pin "5") (pinfunction "2_5") (pintype "passive"))
      (node (ref "U$1") (pin "21") (pinfunction "IO_11_21") (pintype "bidirectional"))
    )
    (net (code "83") (name "P2_DB4") (class "Default")
      (node (ref "RN2") (pin "8") (pinfunction "2_8") (pintype "passive"))
      (node (ref "U$1") (pin "22") (pinfunction "IO_12_22") (pintype "bidirectional"))
    )
    (net (code "84") (name "P2_DB5") (class "Default")
      (node (ref "RN2") (pin "7") (pinfunction "2_7") (pintype "passive"))
      (node (ref "U$1") (pin "23") (pinfunction "IO_13_23") (pintype "bidirectional"))
    )
    (net (code "85") (name "P2_DB6") (class "Default")
      (node (ref "RN2") (pin "6") (pinfunction "2_6") (pintype "passive"))
      (node (ref "U$1") (pin "26") (pinfunction "IO_14_26") (pintype "bidirectional"))
    )
    (net (code "86") (name "P2_DB7") (class "Default")
      (node (ref "RN2") (pin "5") (pinfunction "2_5") (pintype "passive"))
      (node (ref "U$1") (pin "27") (pinfunction "IO_15_27") (pintype "bidirectional"))
    )
    (net (code "87") (name "P2_DB8") (class "Default")
      (node (ref "RN3") (pin "8") (pinfunction "2_8") (pintype "passive"))
      (node (ref "U$1") (pin "28") (pinfunction "IO_16_28") (pintype "bidirectional"))
    )
    (net (code "88") (name "P2_DB9") (class "Default")
      (node (ref "RN3") (pin "7") (pinfunction "2_7") (pintype "passive"))
      (node (ref "U$1") (pin "29") (pinfunction "IO_17_29") (pintype "bidirectional"))
    )
    (net (code "89") (name "P2_DB10") (class "Default")
      (node (ref "RN3") (pin "6") (pinfunction "2_6") (pintype "passive"))
      (node (ref "U$1") (pin "30") (pinfunction "IO_18_30") (pintype "bidirectional"))
    )
    (net (code "90") (name "P2_DB11") (class "Default")
      (node (ref "RN3") (pin "5") (pinfunction "2_5") (pintype "passive"))
      (node (ref "U$1") (pin "31") (pinfunction "IO_19_31") (pintype "bidirectional"))
    )
    (net (code "91") (name "P2_DB12") (class "Default")
      (node (ref "RN4") (pin "6") (pinfunction "2_6") (pintype "passive"))
      (node (ref "U$1") (pin "32") (pinfunction "IO_20_32") (pintype "bidirectional"))
    )
    (net (code "92") (name "P2_DB13") (class "Default")
      (node (ref "RN4") (pin "5") (pinfunction "2_5") (pintype "passive"))
      (node (ref "U$1") (pin "33") (pinfunction "IO_21_33") (pintype "bidirectional"))
    )
    (net (code "93") (name "P2_DB14") (class "Default")
      (node (ref "U$1") (pin "36") (pinfunction "IO_22_36") (pintype "bidirectional"))
    )
    (net (code "94") (name "SWD_CLK") (class "Default")
      (node (ref "IC1") (pin "37") (pinfunction "PA14_37") (pintype "bidirectional"))
      (node (ref "JP2") (pin "3") (pinfunction "3_3") (pintype "passive"))
    )
    (net (code "95") (name "SWD_DIO") (class "Default")
      (node (ref "IC1") (pin "34") (pinfunction "PA13_34") (pintype "bidirectional"))
      (node (ref "JP2") (pin "2") (pinfunction "2_2") (pintype "passive"))
    )
    (net (code "96") (name "USB_DM") (class "Default")
      (node (ref "IC1") (pin "32") (pinfunction "PA11_32") (pintype "bidirectional"))
      (node (ref "R18") (pin "1") (pinfunction "1_1") (pintype "passive"))
    )
    (net (code "97") (name "USB_DP") (class "Default")
      (node (ref "IC1") (pin "33") (pinfunction "PA12_33") (pintype "bidirectional"))
      (node (ref "R17") (pin "1") (pinfunction "1_1") (pintype "passive"))
    )
    (net (code "98") (name "USB_EN") (class "Default")
      (node (ref "IC1") (pin "13") (pinfunction "PA3_13") (pintype "bidirectional"))
      (node (ref "R20") (pin "2") (pinfunction "2_2") (pintype "passive"))
      (node (ref "R21") (pin "1") (pinfunction "1_1") (pintype "passive"))
      (node (ref "U$4") (pin "2") (pinfunction "E_2") (pintype "passive"))
    )
    (net (code "99") (name "unconnected-(IC1A-PA0-WKUP-Pad10)") (class "Default")
      (node (ref "IC1") (pin "10") (pinfunction "PA0-WKUP_10") (pintype "bidirectional"))
    )
    (net (code "100") (name "unconnected-(IC1A-PA1-Pad11)") (class "Default")
      (node (ref "IC1") (pin "11") (pinfunction "PA1_11") (pintype "bidirectional"))
    )
    (net (code "101") (name "unconnected-(IC1A-PA2-Pad12)") (class "Default")
      (node (ref "IC1") (pin "12") (pinfunction "PA2_12") (pintype "bidirectional"))
    )
    (net (code "102") (name "unconnected-(IC1A-PA4-Pad14)") (class "Default")
      (node (ref "IC1") (pin "14") (pinfunction "PA4_14") (pintype "bidirectional"))
    )
    (net (code "103") (name "unconnected-(IC1A-PA5-Pad15)") (class "Default")
      (node (ref "IC1") (pin "15") (pinfunction "PA5_15") (pintype "bidirectional"))
    )
    (net (code "104") (name "unconnected-(IC1A-PA6-Pad16)") (class "Default")
      (node (ref "IC1") (pin "16") (pinfunction "PA6_16") (pintype "bidirectional"))
    )
    (net (code "105") (name "unconnected-(IC1A-PA7-Pad17)") (class "Default")
      (node (ref "IC1") (pin "17") (pinfunction "PA7_17") (pintype "bidirectional"))
    )
    (net (code "106") (name "unconnected-(IC1A-PA8-Pad29)") (class "Default")
      (node (ref "IC1") (pin "29") (pinfunction "PA8_29") (pintype "bidirectional"))
    )
    (net (code "107") (name "unconnected-(IC1A-PA9-Pad30)") (class "Default")
      (node (ref "IC1") (pin "30") (pinfunction "PA9_30") (pintype "bidirectional"))
    )
    (net (code "108") (name "unconnected-(IC1A-PB0-Pad18)") (class "Default")
      (node (ref "IC1") (pin "18") (pinfunction "PB0_18") (pintype "bidirectional"))
    )
    (net (code "109") (name "unconnected-(IC1A-PB1-Pad19)") (class "Default")
      (node (ref "IC1") (pin "19") (pinfunction "PB1_19") (pintype "bidirectional"))
    )
    (net (code "110") (name "unconnected-(IC1A-PB2-Pad20)") (class "Default")
      (node (ref "IC1") (pin "20") (pinfunction "PB2_20") (pintype "bidirectional"))
    )
    (net (code "111") (name "unconnected-(IC1A-PB3-Pad39)") (class "Default")
      (node (ref "IC1") (pin "39") (pinfunction "PB3_39") (pintype "bidirectional"))
    )
    (net (code "112") (name "unconnected-(IC1A-PB4-Pad40)") (class "Default")
      (node (ref "IC1") (pin "40") (pinfunction "PB4_40") (pintype "bidirectional"))
    )
    (net (code "113") (name "unconnected-(IC1A-PB5-Pad41)") (class "Default")
      (node (ref "IC1") (pin "41") (pinfunction "PB5_41") (pintype "bidirectional"))
    )
    (net (code "114") (name "unconnected-(IC1A-PB8-Pad45)") (class "Default")
      (node (ref "IC1") (pin "45") (pinfunction "PB8_45") (pintype "bidirectional"))
    )
    (net (code "115") (name "unconnected-(IC1A-PB9-Pad46)") (class "Default")
      (node (ref "IC1") (pin "46") (pinfunction "PB9_46") (pintype "bidirectional"))
    )
    (net (code "116") (name "unconnected-(IC1A-PB10-Pad21)") (class "Default")
      (node (ref "IC1") (pin "21") (pinfunction "PB10_21") (pintype "bidirectional"))
    )
    (net (code "117") (name "unconnected-(IC1A-PB11-Pad22)") (class "Default")
      (node (ref "IC1") (pin "22") (pinfunction "PB11_22") (pintype "bidirectional"))
    )
    (net (code "118") (name "unconnected-(IC1A-PB12-Pad25)") (class "Default")
      (node (ref "IC1") (pin "25") (pinfunction "PB12_25") (pintype "bidirectional"))
    )
    (net (code "119") (name "unconnected-(IC1A-PB14-Pad27)") (class "Default")
      (node (ref "IC1") (pin "27") (pinfunction "PB14_27") (pintype "bidirectional"))
    )
    (net (code "120") (name "unconnected-(IC1A-PC13-Pad2)") (class "Default")
      (node (ref "IC1") (pin "2") (pinfunction "PC13_2") (pintype "bidirectional"))
    )
    (net (code "121") (name "unconnected-(IC1A-PC14-Pad3)") (class "Default")
      (node (ref "IC1") (pin "3") (pinfunction "PC14_3") (pintype "bidirectional"))
    )
    (net (code "122") (name "unconnected-(IC1A-PC15-Pad4)") (class "Default")
      (node (ref "IC1") (pin "4") (pinfunction "PC15_4") (pintype "bidirectional"))
    )
    (net (code "123") (name "unconnected-(RN8C-1-Pad3)") (class "Default")
      (node (ref "RN8") (pin "3") (pinfunction "1_3") (pintype "passive"))
    )
    (net (code "124") (name "unconnected-(RN8C-2-Pad6)") (class "Default")
      (node (ref "RN8") (pin "6") (pinfunction "2_6") (pintype "passive"))
    )
    (net (code "125") (name "unconnected-(RN8D-1-Pad4)") (class "Default")
      (node (ref "RN8") (pin "4") (pinfunction "1_4") (pintype "passive"))
    )
    (net (code "126") (name "unconnected-(RN8D-2-Pad5)") (class "Default")
      (node (ref "RN8") (pin "5") (pinfunction "2_5") (pintype "passive"))
    )
    (net (code "127") (name "unconnected-(U$1A-CLOCK-Pad55)") (class "Default")
      (node (ref "U$1") (pin "55") (pinfunction "CLOCK_55") (pintype "input"))
    )
    (net (code "128") (name "unconnected-(U$1A-INPUT-Pad56)") (class "Default")
      (node (ref "U$1") (pin "56") (pinfunction "INPUT_56") (pintype "input"))
    )
    (net (code "129") (name "unconnected-(U$1A-INPUT_2-Pad54)") (class "Default")
      (node (ref "U$1") (pin "54") (pinfunction "INPUT_2_54") (pintype "input"))
    )
    (net (code "130") (name "unconnected-(U$1A-IO-Pad72)") (class "Default")
      (node (ref "U$1") (pin "72") (pinfunction "IO_72") (pintype "bidirectional"))
    )
    (net (code "131") (name "unconnected-(U$1A-IO_2-Pad8)") (class "Default")
      (node (ref "U$1") (pin "8") (pinfunction "IO_2_8") (pintype "bidirectional"))
    )
    (net (code "132") (name "unconnected-(U$1A-IO_3-Pad9)") (class "Default")
      (node (ref "U$1") (pin "9") (pinfunction "IO_3_9") (pintype "bidirectional"))
    )
    (net (code "133") (name "unconnected-(U$1A-IO_4-Pad10)") (class "Default")
      (node (ref "U$1") (pin "10") (pinfunction "IO_4_10") (pintype "bidirectional"))
    )
    (net (code "134") (name "unconnected-(U$1A-IO_5-Pad12)") (class "Default")
      (node (ref "U$1") (pin "12") (pinfunction "IO_5_12") (pintype "bidirectional"))
    )
    (net (code "135") (name "unconnected-(U$1A-IO_6-Pad13)") (class "Default")
      (node (ref "U$1") (pin "13") (pinfunction "IO_6_13") (pintype "bidirectional"))
    )
    (net (code "136") (name "unconnected-(U$1A-IO_38-Pad63)") (class "Default")
      (node (ref "U$1") (pin "63") (pinfunction "IO_38_63") (pintype "bidirectional"))
    )
    (net (code "137") (name "unconnected-(U$1A-IO_39-Pad64)") (class "Default")
      (node (ref "U$1") (pin "64") (pinfunction "IO_39_64") (pintype "bidirectional"))
    )
    (net (code "138") (name "unconnected-(U$1A-IO_40-Pad65)") (class "Default")
      (node (ref "U$1") (pin "65") (pinfunction "IO_40_65") (pintype "bidirectional"))
    )
    (net (code "139") (name "unconnected-(U$1A-IO_41-Pad67)") (class "Default")
      (node (ref "U$1") (pin "67") (pinfunction "IO_41_67") (pintype "bidirectional"))
    )
    (net (code "140") (name "unconnected-(U$1A-IO_42-Pad68)") (class "Default")
      (node (ref "U$1") (pin "68") (pinfunction "IO_42_68") (pintype "bidirectional"))
    )
    (net (code "141") (name "unconnected-(U$1A-IO_43-Pad69)") (class "Default")
      (node (ref "U$1") (pin "69") (pinfunction "IO_43_69") (pintype "bidirectional"))
    )
    (net (code "142") (name "unconnected-(U$1A-IO_44-Pad70)") (class "Default")
      (node (ref "U$1") (pin "70") (pinfunction "IO_44_70") (pintype "bidirectional"))
    )
    (net (code "143") (name "unconnected-(U$1A-IO{slash}CLKUSR-Pad7)") (class "Default")
      (node (ref "U$1") (pin "7") (pinfunction "IO/CLKUSR_7") (pintype "bidirectional"))
    )
    (net (code "144") (name "unconnected-(U$1A-IO{slash}RDY{slash}NBSY-Pad11)") (class "Default")
      (node (ref "U$1") (pin "11") (pinfunction "IO/RDY/NBSY_11") (pintype "bidirectional"))
    )
    (net (code "145") (name "unconnected-(U$1A-NCEO-Pad3)") (class "Default")
      (node (ref "U$1") (pin "3") (pinfunction "NCEO_3") (pintype "input"))
    )
    (net (code "146") (name "unconnected-(U$1A-TCK-Pad1)") (class "Default")
      (node (ref "U$1") (pin "1") (pinfunction "TCK_1") (pintype "input"))
    )
    (net (code "147") (name "unconnected-(U$1A-TDO-Pad4)") (class "Default")
      (node (ref "U$1") (pin "4") (pinfunction "TDO_4") (pintype "output"))
    )
    (net (code "148") (name "unconnected-(U$1A-TMS-Pad34)") (class "Default")
      (node (ref "U$1") (pin "34") (pinfunction "TMS_34") (pintype "input"))
    )
    (net (code "149") (name "unconnected-(U$1B-INPUT-Pad126)") (class "Default")
      (node (ref "U$1") (pin "126") (pinfunction "INPUT_126") (pintype "input"))
    )
    (net (code "150") (name "unconnected-(U$1B-INPUT_2-Pad124)") (class "Default")
      (node (ref "U$1") (pin "124") (pinfunction "INPUT_2_124") (pintype "input"))
    )
    (net (code "151") (name "unconnected-(U$1B-IO-Pad140)") (class "Default")
      (node (ref "U$1") (pin "140") (pinfunction "IO_140") (pintype "bidirectional"))
    )
    (net (code "152") (name "unconnected-(U$1B-IO_2-Pad73)") (class "Default")
      (node (ref "U$1") (pin "73") (pinfunction "IO_2_73") (pintype "bidirectional"))
    )
    (net (code "153") (name "unconnected-(U$1B-IO_3-Pad78)") (class "Default")
      (node (ref "U$1") (pin "78") (pinfunction "IO_3_78") (pintype "bidirectional"))
    )
    (net (code "154") (name "unconnected-(U$1B-IO_4-Pad79)") (class "Default")
      (node (ref "U$1") (pin "79") (pinfunction "IO_4_79") (pintype "bidirectional"))
    )
    (net (code "155") (name "unconnected-(U$1B-IO_5-Pad80)") (class "Default")
      (node (ref "U$1") (pin "80") (pinfunction "IO_5_80") (pintype "bidirectional"))
    )
    (net (code "156") (name "unconnected-(U$1B-IO_6-Pad81)") (class "Default")
      (node (ref "U$1") (pin "81") (pinfunction "IO_6_81") (pintype "bidirectional"))
    )
    (net (code "157") (name "unconnected-(U$1B-IO_7-Pad82)") (class "Default")
      (node (ref "U$1") (pin "82") (pinfunction "IO_7_82") (pintype "bidirectional"))
    )
    (net (code "158") (name "unconnected-(U$1B-IO_8-Pad83)") (class "Default")
      (node (ref "U$1") (pin "83") (pinfunction "IO_8_83") (pintype "bidirectional"))
    )
    (net (code "159") (name "unconnected-(U$1B-IO_9-Pad86)") (class "Default")
      (node (ref "U$1") (pin "86") (pinfunction "IO_9_86") (pintype "bidirectional"))
    )
    (net (code "160") (name "unconnected-(U$1B-IO_10-Pad87)") (class "Default")
      (node (ref "U$1") (pin "87") (pinfunction "IO_10_87") (pintype "bidirectional"))
    )
    (net (code "161") (name "unconnected-(U$1B-IO_11-Pad88)") (class "Default")
      (node (ref "U$1") (pin "88") (pinfunction "IO_11_88") (pintype "bidirectional"))
    )
    (net (code "162") (name "unconnected-(U$1B-IO_12-Pad89)") (class "Default")
      (node (ref "U$1") (pin "89") (pinfunction "IO_12_89") (pintype "bidirectional"))
    )
    (net (code "163") (name "unconnected-(U$1B-IO_13-Pad90)") (class "Default")
      (node (ref "U$1") (pin "90") (pinfunction "IO_13_90") (pintype "bidirectional"))
    )
    (net (code "164") (name "unconnected-(U$1B-IO_14-Pad91)") (class "Default")
      (node (ref "U$1") (pin "91") (pinfunction "IO_14_91") (pintype "bidirectional"))
    )
    (net (code "165") (name "unconnected-(U$1B-IO_15-Pad92)") (class "Default")
      (node (ref "U$1") (pin "92") (pinfunction "IO_15_92") (pintype "bidirectional"))
    )
    (net (code "166") (name "unconnected-(U$1B-IO_16-Pad95)") (class "Default")
      (node (ref "U$1") (pin "95") (pinfunction "IO_16_95") (pintype "bidirectional"))
    )
    (net (code "167") (name "unconnected-(U$1B-IO_17-Pad96)") (class "Default")
      (node (ref "U$1") (pin "96") (pinfunction "IO_17_96") (pintype "bidirectional"))
    )
    (net (code "168") (name "unconnected-(U$1B-IO_18-Pad97)") (class "Default")
      (node (ref "U$1") (pin "97") (pinfunction "IO_18_97") (pintype "bidirectional"))
    )
    (net (code "169") (name "unconnected-(U$1B-IO_19-Pad98)") (class "Default")
      (node (ref "U$1") (pin "98") (pinfunction "IO_19_98") (pintype "bidirectional"))
    )
    (net (code "170") (name "unconnected-(U$1B-IO_20-Pad99)") (class "Default")
      (node (ref "U$1") (pin "99") (pinfunction "IO_20_99") (pintype "bidirectional"))
    )
    (net (code "171") (name "unconnected-(U$1B-IO_21-Pad100)") (class "Default")
      (node (ref "U$1") (pin "100") (pinfunction "IO_21_100") (pintype "bidirectional"))
    )
    (net (code "172") (name "unconnected-(U$1B-IO_22-Pad101)") (class "Default")
      (node (ref "U$1") (pin "101") (pinfunction "IO_22_101") (pintype "bidirectional"))
    )
    (net (code "173") (name "unconnected-(U$1B-IO_23-Pad102)") (class "Default")
      (node (ref "U$1") (pin "102") (pinfunction "IO_23_102") (pintype "bidirectional"))
    )
    (net (code "174") (name "unconnected-(U$1B-IO_24-Pad117)") (class "Default")
      (node (ref "U$1") (pin "117") (pinfunction "IO_24_117") (pintype "bidirectional"))
    )
    (net (code "175") (name "unconnected-(U$1B-IO_25-Pad118)") (class "Default")
      (node (ref "U$1") (pin "118") (pinfunction "IO_25_118") (pintype "bidirectional"))
    )
    (net (code "176") (name "unconnected-(U$1B-IO_26-Pad119)") (class "Default")
      (node (ref "U$1") (pin "119") (pinfunction "IO_26_119") (pintype "bidirectional"))
    )
    (net (code "177") (name "unconnected-(U$1B-IO_27-Pad120)") (class "Default")
      (node (ref "U$1") (pin "120") (pinfunction "IO_27_120") (pintype "bidirectional"))
    )
    (net (code "178") (name "unconnected-(U$1B-IO_28-Pad121)") (class "Default")
      (node (ref "U$1") (pin "121") (pinfunction "IO_28_121") (pintype "bidirectional"))
    )
    (net (code "179") (name "unconnected-(U$1B-IO_29-Pad130)") (class "Default")
      (node (ref "U$1") (pin "130") (pinfunction "IO_29_130") (pintype "bidirectional"))
    )
    (net (code "180") (name "unconnected-(U$1B-IO_30-Pad131)") (class "Default")
      (node (ref "U$1") (pin "131") (pinfunction "IO_30_131") (pintype "bidirectional"))
    )
    (net (code "181") (name "unconnected-(U$1B-IO_31-Pad132)") (class "Default")
      (node (ref "U$1") (pin "132") (pinfunction "IO_31_132") (pintype "bidirectional"))
    )
    (net (code "182") (name "unconnected-(U$1B-IO_32-Pad133)") (class "Default")
      (node (ref "U$1") (pin "133") (pinfunction "IO_32_133") (pintype "bidirectional"))
    )
    (net (code "183") (name "unconnected-(U$1B-IO_33-Pad135)") (class "Default")
      (node (ref "U$1") (pin "135") (pinfunction "IO_33_135") (pintype "bidirectional"))
    )
    (net (code "184") (name "unconnected-(U$1B-IO_34-Pad136)") (class "Default")
      (node (ref "U$1") (pin "136") (pinfunction "IO_34_136") (pintype "bidirectional"))
    )
    (net (code "185") (name "unconnected-(U$1B-IO_35-Pad137)") (class "Default")
      (node (ref "U$1") (pin "137") (pinfunction "IO_35_137") (pintype "bidirectional"))
    )
    (net (code "186") (name "unconnected-(U$1B-IO_36-Pad138)") (class "Default")
      (node (ref "U$1") (pin "138") (pinfunction "IO_36_138") (pintype "bidirectional"))
    )
    (net (code "187") (name "unconnected-(U$1B-IO{slash}CS-Pad143)") (class "Default")
      (node (ref "U$1") (pin "143") (pinfunction "IO/CS_143") (pintype "bidirectional"))
    )
    (net (code "188") (name "unconnected-(U$1B-IO{slash}DATA1-Pad109)") (class "Default")
      (node (ref "U$1") (pin "109") (pinfunction "IO/DATA1_109") (pintype "bidirectional"))
    )
    (net (code "189") (name "unconnected-(U$1B-IO{slash}DATA2-Pad110)") (class "Default")
      (node (ref "U$1") (pin "110") (pinfunction "IO/DATA2_110") (pintype "bidirectional"))
    )
    (net (code "190") (name "unconnected-(U$1B-IO{slash}DATA3-Pad111)") (class "Default")
      (node (ref "U$1") (pin "111") (pinfunction "IO/DATA3_111") (pintype "bidirectional"))
    )
    (net (code "191") (name "unconnected-(U$1B-IO{slash}DATA4-Pad112)") (class "Default")
      (node (ref "U$1") (pin "112") (pinfunction "IO/DATA4_112") (pintype "bidirectional"))
    )
    (net (code "192") (name "unconnected-(U$1B-IO{slash}DATA5-Pad113)") (class "Default")
      (node (ref "U$1") (pin "113") (pinfunction "IO/DATA5_113") (pintype "bidirectional"))
    )
    (net (code "193") (name "unconnected-(U$1B-IO{slash}DATA6-Pad114)") (class "Default")
      (node (ref "U$1") (pin "114") (pinfunction "IO/DATA6_114") (pintype "bidirectional"))
    )
    (net (code "194") (name "unconnected-(U$1B-IO{slash}DATA7-Pad116)") (class "Default")
      (node (ref "U$1") (pin "116") (pinfunction "IO/DATA7_116") (pintype "bidirectional"))
    )
    (net (code "195") (name "unconnected-(U$1B-IO{slash}DEV_CLRN-Pad122)") (class "Default")
      (node (ref "U$1") (pin "122") (pinfunction "IO/DEV_CLRN_122") (pintype "bidirectional"))
    )
    (net (code "196") (name "unconnected-(U$1B-IO{slash}DEV_OE-Pad128)") (class "Default")
      (node (ref "U$1") (pin "128") (pinfunction "IO/DEV_OE_128") (pintype "bidirectional"))
    )
    (net (code "197") (name "unconnected-(U$1B-IO{slash}NCS-Pad144)") (class "Default")
      (node (ref "U$1") (pin "144") (pinfunction "IO/NCS_144") (pintype "bidirectional"))
    )
    (net (code "198") (name "unconnected-(U$1B-IO{slash}NRS-Pad141)") (class "Default")
      (node (ref "U$1") (pin "141") (pinfunction "IO/NRS_141") (pintype "bidirectional"))
    )
    (net (code "199") (name "unconnected-(U$1B-IO{slash}NWS-Pad142)") (class "Default")
      (node (ref "U$1") (pin "142") (pinfunction "IO/NWS_142") (pintype "bidirectional"))
    )
    (net (code "200") (name "unconnected-(U$1B-TDI-Pad105)") (class "Default")
      (node (ref "U$1") (pin "105") (pinfunction "TDI_105") (pintype "input"))
    )
  )
)
